# HiSpeedADC2.net
KiCad netlist of a schematic drawn in Altium Designer
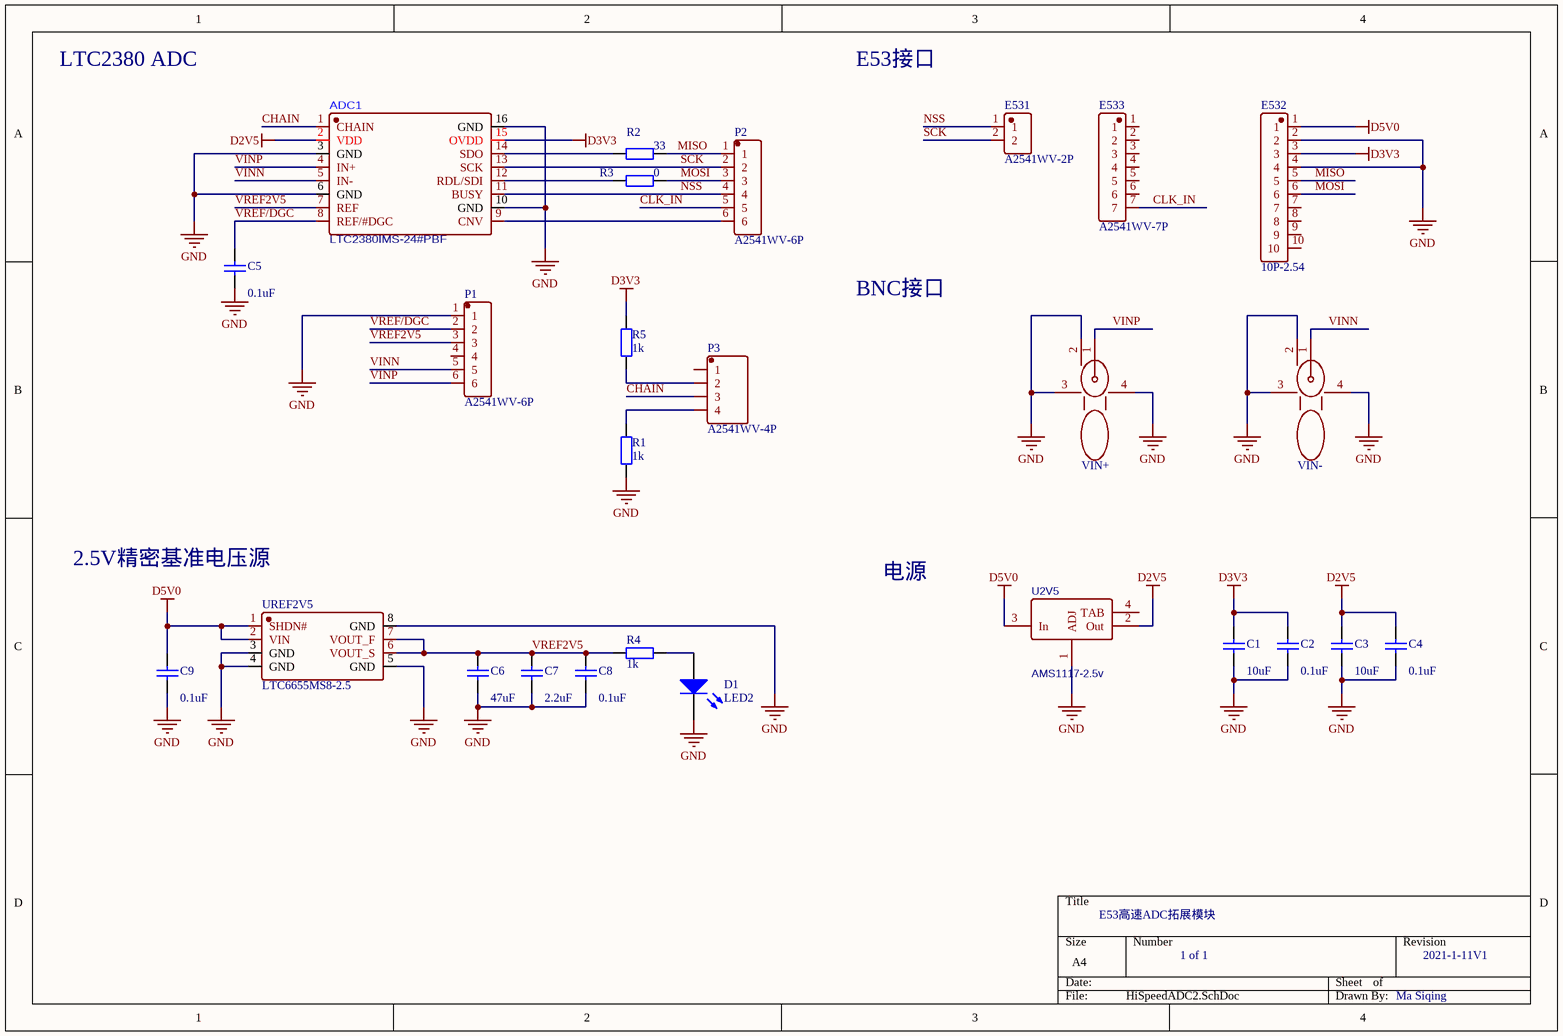
[diagram p0: HiSpeedADC2.SchDoc]

(export (version "E")
  (design (tool "Eeschema 10.0.6"))
  (components
    (comp (ref "ADC1")
      (value "LTC2380IMS-24#PBF")
      (footprint "MSOP-16_L4.0-W3.0-P0.50-LS4.9-BL")
      (libsource (lib "NBIoT") (part "LTC2380IMS-24#PBF"))
    )
    (comp (ref "C1")
      (value "10uF")
      (footprint "C1206")
      (description "Capacitor (Semiconductor SIM Model)")
      (fields (field (name "PUBLISHER") "Altium Limited"))
      (libsource (lib "Miscellaneous Devices") (part "Cap Semi"))
    )
    (comp (ref "C2")
      (value "0.1uF")
      (footprint "C1206")
      (description "Capacitor (Semiconductor SIM Model)")
      (fields (field (name "PUBLISHER") "Altium Limited"))
      (libsource (lib "Miscellaneous Devices") (part "Cap Semi"))
    )
    (comp (ref "C3")
      (value "10uF")
      (footprint "C1206")
      (description "Capacitor (Semiconductor SIM Model)")
      (fields (field (name "PUBLISHER") "Altium Limited"))
      (libsource (lib "Miscellaneous Devices") (part "Cap Semi"))
    )
    (comp (ref "C4")
      (value "0.1uF")
      (footprint "C1206")
      (description "Capacitor (Semiconductor SIM Model)")
      (fields (field (name "PUBLISHER") "Altium Limited"))
      (libsource (lib "Miscellaneous Devices") (part "Cap Semi"))
    )
    (comp (ref "C5")
      (value "0.1uF")
      (footprint "C1206")
      (description "Capacitor (Semiconductor SIM Model)")
      (fields (field (name "PUBLISHER") "Altium Limited"))
      (libsource (lib "Miscellaneous Devices") (part "Cap Semi"))
    )
    (comp (ref "C6")
      (value "47uF")
      (footprint "C1206")
      (description "Capacitor (Semiconductor SIM Model)")
      (fields (field (name "PUBLISHER") "Altium Limited"))
      (libsource (lib "Miscellaneous Devices") (part "Cap Semi"))
    )
    (comp (ref "C7")
      (value "2.2uF")
      (footprint "C1206")
      (description "Capacitor (Semiconductor SIM Model)")
      (fields (field (name "PUBLISHER") "Altium Limited"))
      (libsource (lib "Miscellaneous Devices") (part "Cap Semi"))
    )
    (comp (ref "C8")
      (value "0.1uF")
      (footprint "C1206")
      (description "Capacitor (Semiconductor SIM Model)")
      (fields (field (name "PUBLISHER") "Altium Limited"))
      (libsource (lib "Miscellaneous Devices") (part "Cap Semi"))
    )
    (comp (ref "C9")
      (value "0.1uF")
      (footprint "C1206")
      (description "Capacitor (Semiconductor SIM Model)")
      (fields (field (name "PUBLISHER") "Altium Limited"))
      (libsource (lib "Miscellaneous Devices") (part "Cap Semi"))
    )
    (comp (ref "D1")
      (value "LED2")
      (footprint "3.2X1.6X1.1")
      (description "Typical RED, GREEN, YELLOW, AMBER GaAs LED")
      (fields (field (name "PUBLISHER") "Altium Limited"))
      (libsource (lib "Miscellaneous Devices") (part "LED2"))
    )
    (comp (ref "E531")
      (value "A2541WV-2P")
      (footprint "HDR-TH_P2.54-H-M_A2541WV-2P")
      (libsource (lib "NBIoT") (part "A2541WV-2P"))
    )
    (comp (ref "E532")
      (value "10P-2.54")
      (footprint "HDR-TH_10P-P2.54-V")
      (libsource (lib "NBIoT") (part "10P-2.54"))
    )
    (comp (ref "E533")
      (value "A2541WV-7P")
      (footprint "HDR-TH_7P-P2.54-V")
      (libsource (lib "NBIoT") (part "A2541WV-7P"))
    )
    (comp (ref "P1")
      (value "A2541WV-6P")
      (footprint "HDR-TH_6P-P2.54-V")
      (libsource (lib "NBIoT") (part "A2541WV-6P"))
    )
    (comp (ref "P2")
      (value "A2541WV-6P")
      (footprint "HDR-TH_6P-P2.54-V")
      (libsource (lib "NBIoT") (part "A2541WV-6P"))
    )
    (comp (ref "P3")
      (value "A2541WV-4P")
      (footprint "HDR-TH_4P-P2.54-V")
      (libsource (lib "NBIoT") (part "A2541WV-4P"))
    )
    (comp (ref "R1")
      (value "1k")
      (footprint "0805_R")
      (description "0805贴片电阻")
      (libsource (lib "") (part "Res_0805_1"))
    )
    (comp (ref "R2")
      (value "33")
      (footprint "0805_R")
      (description "0805贴片电阻")
      (libsource (lib "02-Miscellaneous_Devices_ZSF_Library") (part "Res_0805"))
    )
    (comp (ref "R3")
      (value "0")
      (footprint "0805_R")
      (description "0805贴片电阻")
      (libsource (lib "02-Miscellaneous_Devices_ZSF_Library") (part "Res_0805"))
    )
    (comp (ref "R4")
      (value "1k")
      (footprint "0805_R")
      (description "0805贴片电阻")
      (libsource (lib "02-Miscellaneous_Devices_ZSF_Library") (part "Res_0805"))
    )
    (comp (ref "R5")
      (value "1k")
      (footprint "0805_R")
      (description "0805贴片电阻")
      (libsource (lib "") (part "Res_0805_1"))
    )
    (comp (ref "U2V5")
      (value "AMS1117-2.5v")
      (footprint "SOT-223_L6.7-W3.5-P2.30-BR")
      (fields
        (field (name "BOM_MANUFACTURER PART") "AMS1117-ADJ")
        (field (name "BOM_SUPPLIER PART") "C6188")
        (field (name "CONTRIBUTOR") "GerryChen")
      )
      (libsource (lib "NBIoT") (part "AMS1117-ADJ"))
    )
    (comp (ref "UREF2V5")
      (value "LTC6655MS8-2.5")
      (footprint "MSOP-8_L3.0-W3.0-P0.65-LS4.9-BL")
      (libsource (lib "NBIoT") (part "LTC6655MS8-5"))
    )
    (comp (ref "VIN+")
      (value "BNC1")
      (footprint "BNC-TH_DOSIN-801-0072")
      (libsource (lib "NBIoT") (part "BNC"))
    )
    (comp (ref "VIN-")
      (value "BNC")
      (footprint "BNC-TH_DOSIN-801-0072")
      (libsource (lib "NBIoT") (part "BNC"))
    )
  )
  (nets
    (net (code "1") (name "/CHAIN") (class "Default")
      (node (ref "ADC1") (pin "1") (pinfunction "CHAIN_1") (pintype "passive"))
      (node (ref "P3") (pin "3") (pinfunction "3_3") (pintype "passive"))
    )
    (net (code "2") (name "/CLK_IN") (class "Default")
      (node (ref "E533") (pin "7") (pinfunction "7_7") (pintype "passive"))
      (node (ref "P2") (pin "5") (pinfunction "5_5") (pintype "passive"))
    )
    (net (code "3") (name "/MISO") (class "Default")
      (node (ref "E532") (pin "5") (pinfunction "5_5") (pintype "passive"))
      (node (ref "P2") (pin "1") (pinfunction "1_1") (pintype "passive"))
      (node (ref "R2") (pin "2") (pinfunction "2_2") (pintype "passive"))
    )
    (net (code "4") (name "/MOSI") (class "Default")
      (node (ref "E532") (pin "6") (pinfunction "6_6") (pintype "passive"))
      (node (ref "P2") (pin "3") (pinfunction "3_3") (pintype "passive"))
      (node (ref "R3") (pin "2") (pinfunction "2_2") (pintype "passive"))
    )
    (net (code "5") (name "/NSS") (class "Default")
      (node (ref "ADC1") (pin "11") (pinfunction "BUSY_11") (pintype "passive"))
      (node (ref "E531") (pin "1") (pinfunction "1_1") (pintype "passive"))
      (node (ref "P2") (pin "4") (pinfunction "4_4") (pintype "passive"))
    )
    (net (code "6") (name "/SCK") (class "Default")
      (node (ref "ADC1") (pin "13") (pinfunction "SCK_13") (pintype "passive"))
      (node (ref "E531") (pin "2") (pinfunction "2_2") (pintype "passive"))
      (node (ref "P2") (pin "2") (pinfunction "2_2") (pintype "passive"))
    )
    (net (code "7") (name "/VINN") (class "Default")
      (node (ref "ADC1") (pin "5") (pinfunction "IN-_5") (pintype "passive"))
      (node (ref "P1") (pin "5") (pinfunction "5_5") (pintype "passive"))
      (node (ref "VIN-") (pin "1") (pinfunction "1_1") (pintype "passive"))
    )
    (net (code "8") (name "/VINP") (class "Default")
      (node (ref "ADC1") (pin "4") (pinfunction "IN+_4") (pintype "passive"))
      (node (ref "P1") (pin "6") (pinfunction "6_6") (pintype "passive"))
      (node (ref "VIN+") (pin "1") (pinfunction "1_1") (pintype "passive"))
    )
    (net (code "9") (name "/VREF2V5") (class "Default")
      (node (ref "ADC1") (pin "7") (pinfunction "REF_7") (pintype "passive"))
      (node (ref "C6") (pin "1") (pinfunction "1_1") (pintype "passive"))
      (node (ref "C7") (pin "1") (pinfunction "1_1") (pintype "passive"))
      (node (ref "C8") (pin "1") (pinfunction "1_1") (pintype "passive"))
      (node (ref "P1") (pin "3") (pinfunction "3_3") (pintype "passive"))
      (node (ref "R4") (pin "1") (pinfunction "1_1") (pintype "passive"))
      (node (ref "UREF2V5") (pin "6") (pinfunction "VOUT_S_6") (pintype "passive"))
      (node (ref "UREF2V5") (pin "7") (pinfunction "VOUT_F_7") (pintype "passive"))
    )
    (net (code "10") (name "/VREF{slash}DGC") (class "Default")
      (node (ref "ADC1") (pin "8") (pinfunction "REF/#DGC_8") (pintype "passive"))
      (node (ref "C5") (pin "1") (pinfunction "1_1") (pintype "passive"))
      (node (ref "P1") (pin "2") (pinfunction "2_2") (pintype "passive"))
    )
    (net (code "11") (name "D2V5") (class "Default")
      (node (ref "ADC1") (pin "2") (pinfunction "VDD_2") (pintype "passive"))
      (node (ref "C3") (pin "1") (pinfunction "1_1") (pintype "passive"))
      (node (ref "C4") (pin "1") (pinfunction "1_1") (pintype "passive"))
      (node (ref "U2V5") (pin "2") (pinfunction "Out_2") (pintype "passive"))
    )
    (net (code "12") (name "D3V3") (class "Default")
      (node (ref "ADC1") (pin "15") (pinfunction "OVDD_15") (pintype "passive"))
      (node (ref "C1") (pin "1") (pinfunction "1_1") (pintype "passive"))
      (node (ref "C2") (pin "1") (pinfunction "1_1") (pintype "passive"))
      (node (ref "E532") (pin "3") (pinfunction "3_3") (pintype "passive"))
      (node (ref "R5") (pin "2") (pinfunction "2_2") (pintype "passive"))
    )
    (net (code "13") (name "D5V0") (class "Default")
      (node (ref "C9") (pin "1") (pinfunction "1_1") (pintype "passive"))
      (node (ref "E532") (pin "1") (pinfunction "1_1") (pintype "passive"))
      (node (ref "U2V5") (pin "3") (pinfunction "In_3") (pintype "passive"))
      (node (ref "UREF2V5") (pin "1") (pinfunction "SHDN#_1") (pintype "passive"))
      (node (ref "UREF2V5") (pin "2") (pinfunction "VIN_2") (pintype "passive"))
    )
    (net (code "14") (name "GND") (class "Default")
      (node (ref "ADC1") (pin "10") (pinfunction "GND_10") (pintype "passive"))
      (node (ref "ADC1") (pin "16") (pinfunction "GND_16") (pintype "passive"))
      (node (ref "ADC1") (pin "3") (pinfunction "GND_3") (pintype "passive"))
      (node (ref "ADC1") (pin "6") (pinfunction "GND_6") (pintype "passive"))
      (node (ref "C1") (pin "2") (pinfunction "2_2") (pintype "passive"))
      (node (ref "C2") (pin "2") (pinfunction "2_2") (pintype "passive"))
      (node (ref "C3") (pin "2") (pinfunction "2_2") (pintype "passive"))
      (node (ref "C4") (pin "2") (pinfunction "2_2") (pintype "passive"))
      (node (ref "C5") (pin "2") (pinfunction "2_2") (pintype "passive"))
      (node (ref "C6") (pin "2") (pinfunction "2_2") (pintype "passive"))
      (node (ref "C7") (pin "2") (pinfunction "2_2") (pintype "passive"))
      (node (ref "C8") (pin "2") (pinfunction "2_2") (pintype "passive"))
      (node (ref "C9") (pin "2") (pinfunction "2_2") (pintype "passive"))
      (node (ref "D1") (pin "2") (pinfunction "K_2") (pintype "passive"))
      (node (ref "E532") (pin "2") (pinfunction "2_2") (pintype "passive"))
      (node (ref "E532") (pin "4") (pinfunction "4_4") (pintype "passive"))
      (node (ref "P1") (pin "1") (pinfunction "1_1") (pintype "passive"))
      (node (ref "R1") (pin "1") (pinfunction "1_1") (pintype "passive"))
      (node (ref "U2V5") (pin "1") (pinfunction "ADJ_1") (pintype "passive"))
      (node (ref "UREF2V5") (pin "3") (pinfunction "GND_3") (pintype "passive"))
      (node (ref "UREF2V5") (pin "4") (pinfunction "GND_4") (pintype "passive"))
      (node (ref "UREF2V5") (pin "5") (pinfunction "GND_5") (pintype "passive"))
      (node (ref "UREF2V5") (pin "8") (pinfunction "GND_8") (pintype "passive"))
      (node (ref "VIN+") (pin "2") (pinfunction "2_2") (pintype "passive"))
      (node (ref "VIN+") (pin "3") (pinfunction "3_3") (pintype "passive"))
      (node (ref "VIN+") (pin "4") (pinfunction "4_4") (pintype "passive"))
      (node (ref "VIN-") (pin "2") (pinfunction "2_2") (pintype "passive"))
      (node (ref "VIN-") (pin "3") (pinfunction "3_3") (pintype "passive"))
      (node (ref "VIN-") (pin "4") (pinfunction "4_4") (pintype "passive"))
    )
    (net (code "15") (name "Net-(ADC1-CNV)") (class "Default")
      (node (ref "ADC1") (pin "9") (pinfunction "CNV_9") (pintype "passive"))
      (node (ref "P2") (pin "6") (pinfunction "6_6") (pintype "passive"))
    )
    (net (code "16") (name "Net-(ADC1-RDL{slash}SDI)") (class "Default")
      (node (ref "ADC1") (pin "12") (pinfunction "RDL/SDI_12") (pintype "passive"))
      (node (ref "R3") (pin "1") (pinfunction "1_1") (pintype "passive"))
    )
    (net (code "17") (name "Net-(ADC1-SDO)") (class "Default")
      (node (ref "ADC1") (pin "14") (pinfunction "SDO_14") (pintype "passive"))
      (node (ref "R2") (pin "1") (pinfunction "1_1") (pintype "passive"))
    )
    (net (code "18") (name "Net-(D1-A)") (class "Default")
      (node (ref "D1") (pin "1") (pinfunction "A_1") (pintype "passive"))
      (node (ref "R4") (pin "2") (pinfunction "2_2") (pintype "passive"))
    )
    (net (code "19") (name "Net-(P3-Pad2)") (class "Default")
      (node (ref "P3") (pin "2") (pinfunction "2_2") (pintype "passive"))
      (node (ref "R5") (pin "1") (pinfunction "1_1") (pintype "passive"))
    )
    (net (code "20") (name "Net-(P3-Pad4)") (class "Default")
      (node (ref "P3") (pin "4") (pinfunction "4_4") (pintype "passive"))
      (node (ref "R1") (pin "2") (pinfunction "2_2") (pintype "passive"))
    )
    (net (code "21") (name "unconnected-(E532-Pad7)") (class "Default")
      (node (ref "E532") (pin "7") (pinfunction "7_7") (pintype "passive"))
    )
    (net (code "22") (name "unconnected-(E532-Pad8)") (class "Default")
      (node (ref "E532") (pin "8") (pinfunction "8_8") (pintype "passive"))
    )
    (net (code "23") (name "unconnected-(E532-Pad9)") (class "Default")
      (node (ref "E532") (pin "9") (pinfunction "9_9") (pintype "passive"))
    )
    (net (code "24") (name "unconnected-(E532-Pad10)") (class "Default")
      (node (ref "E532") (pin "10") (pinfunction "10_10") (pintype "passive"))
    )
    (net (code "25") (name "unconnected-(E533-Pad1)") (class "Default")
      (node (ref "E533") (pin "1") (pinfunction "1_1") (pintype "passive"))
    )
    (net (code "26") (name "unconnected-(E533-Pad2)") (class "Default")
      (node (ref "E533") (pin "2") (pinfunction "2_2") (pintype "passive"))
    )
    (net (code "27") (name "unconnected-(E533-Pad3)") (class "Default")
      (node (ref "E533") (pin "3") (pinfunction "3_3") (pintype "passive"))
    )
    (net (code "28") (name "unconnected-(E533-Pad4)") (class "Default")
      (node (ref "E533") (pin "4") (pinfunction "4_4") (pintype "passive"))
    )
    (net (code "29") (name "unconnected-(E533-Pad5)") (class "Default")
      (node (ref "E533") (pin "5") (pinfunction "5_5") (pintype "passive"))
    )
    (net (code "30") (name "unconnected-(E533-Pad6)") (class "Default")
      (node (ref "E533") (pin "6") (pinfunction "6_6") (pintype "passive"))
    )
    (net (code "31") (name "unconnected-(P1-Pad4)") (class "Default")
      (node (ref "P1") (pin "4") (pinfunction "4_4") (pintype "passive"))
    )
    (net (code "32") (name "unconnected-(P3-Pad1)") (class "Default")
      (node (ref "P3") (pin "1") (pinfunction "1_1") (pintype "passive"))
    )
    (net (code "33") (name "unconnected-(U2V5-TAB-Pad4)") (class "Default")
      (node (ref "U2V5") (pin "4") (pinfunction "TAB_4") (pintype "passive"))
    )
  )
)
